# test2_3schematic.net
KiCad netlist of a schematic drawn in EAGLE
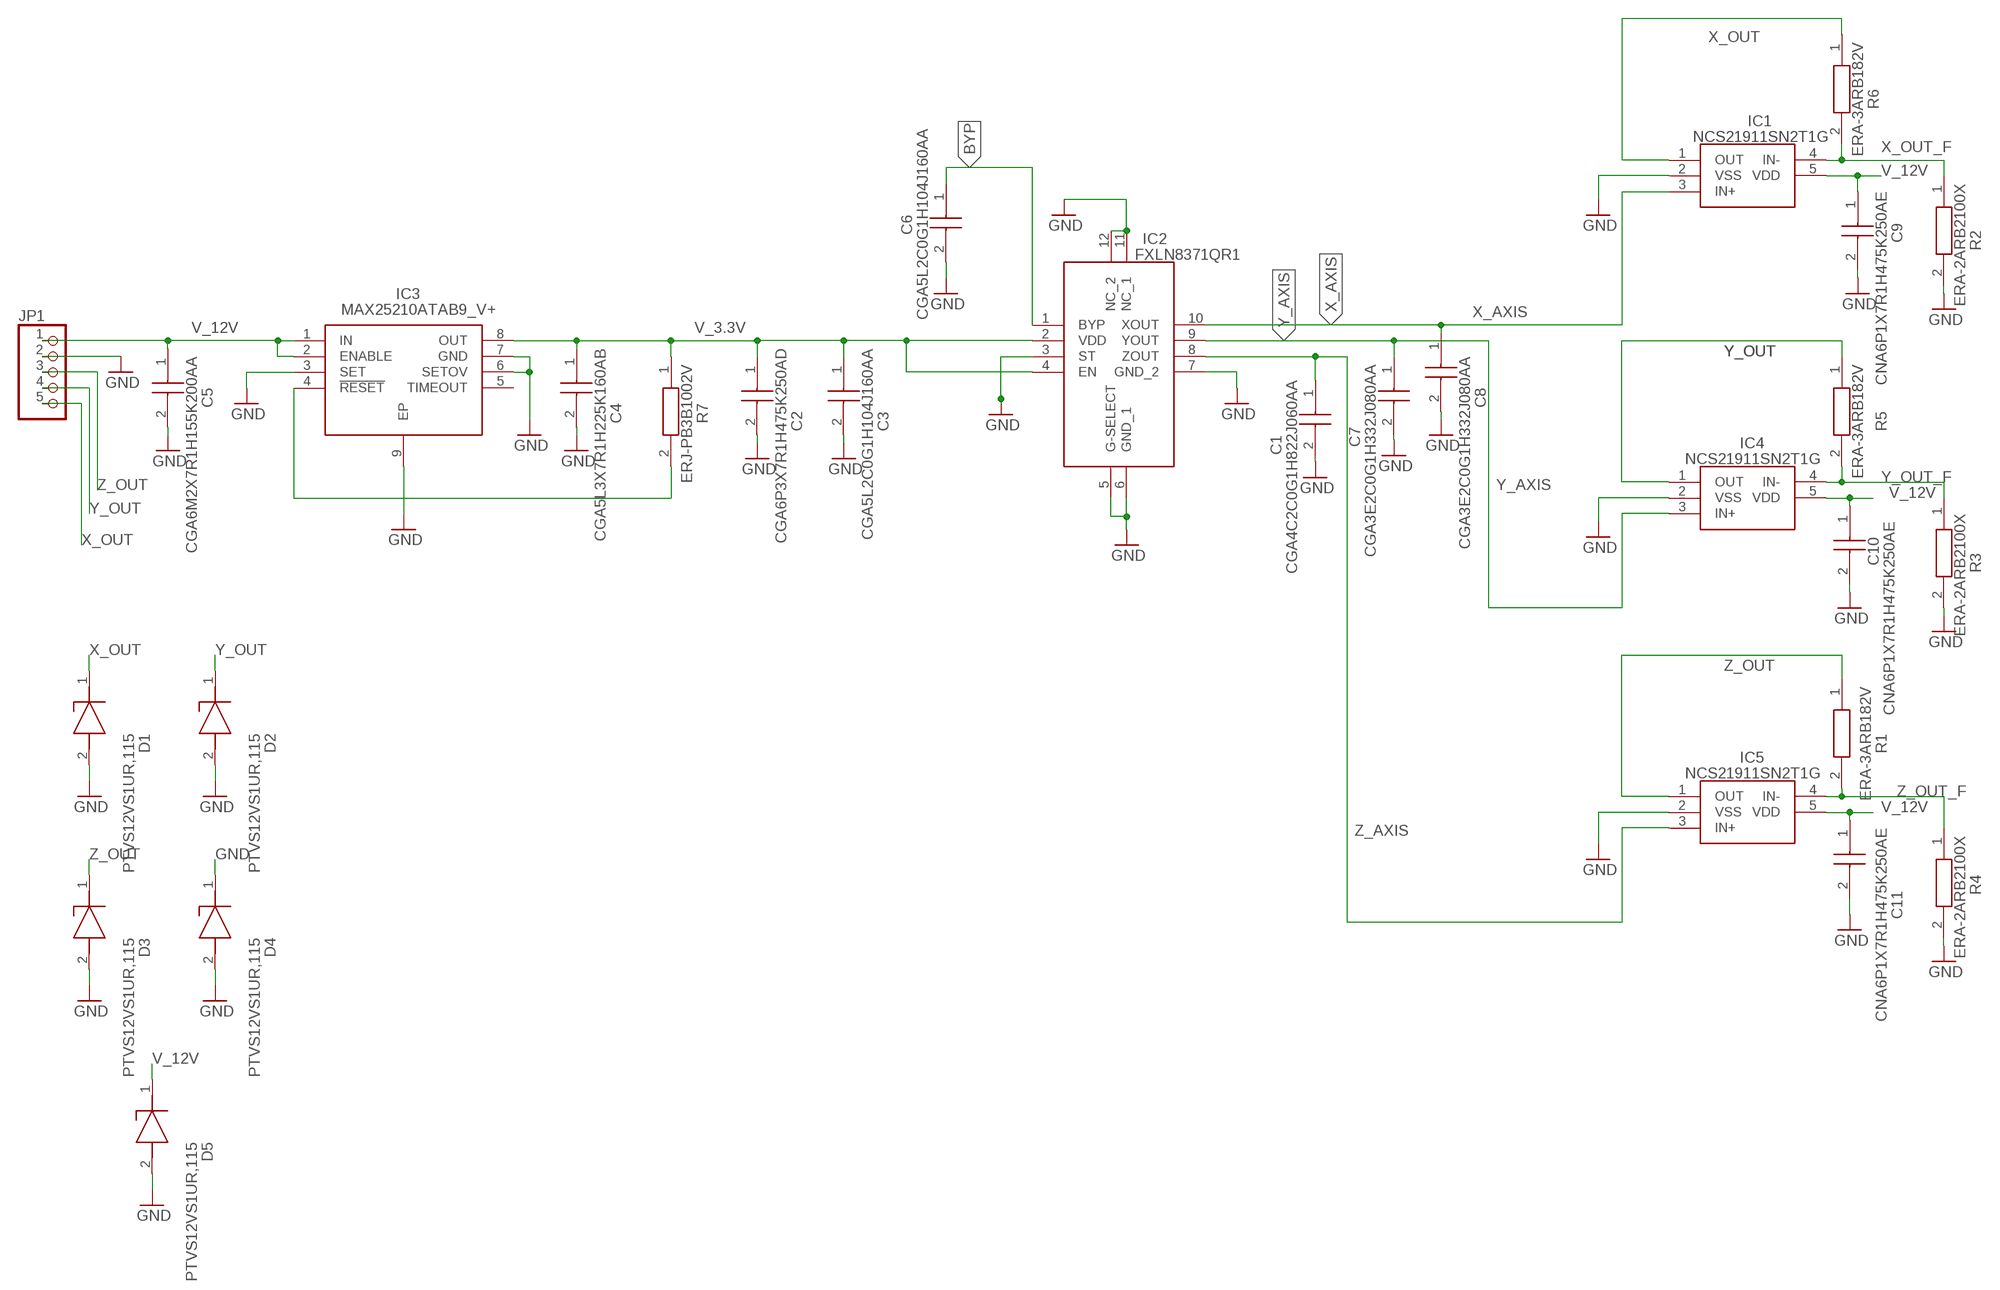
[diagram p0: schematic, sheet 1]

(export (version "E")
  (design (tool "Eeschema 10.0.6"))
  (components
    (comp (ref "C1")
      (value "CGA4C2C0G1H822J060AA")
      (footprint "eagle-import:CAPC2012X145N")
      (libsource (lib "eagle-import") (part "CGA4C2C0G1H822J060AA"))
    )
    (comp (ref "C2")
      (value "CGA6P3X7R1H475K250AD")
      (footprint "eagle-import:CAPC3225X280N")
      (libsource (lib "eagle-import") (part "CGA6P3X7R1H475K250AD"))
    )
    (comp (ref "C3")
      (value "CGA5L2C0G1H104J160AA")
      (footprint "eagle-import:CAPC3216X180N")
      (libsource (lib "eagle-import") (part "CGA5L2C0G1H104J160AA"))
    )
    (comp (ref "C4")
      (value "CGA5L3X7R1H225K160AB")
      (footprint "eagle-import:CAPC3317X190N")
      (libsource (lib "eagle-import") (part "CGA5L3X7R1H225K160AB"))
    )
    (comp (ref "C5")
      (value "CGA6M2X7R1H155K200AA")
      (footprint "eagle-import:CAPC3225X220N")
      (libsource (lib "eagle-import") (part "CGA6M2X7R1H155K200AA"))
    )
    (comp (ref "C6")
      (value "CGA5L2C0G1H104J160AA")
      (footprint "eagle-import:CAPC3216X180N")
      (libsource (lib "eagle-import") (part "CGA5L2C0G1H104J160AA"))
    )
    (comp (ref "C7")
      (value "CGA3E2C0G1H332J080AA")
      (footprint "eagle-import:CAPC1608X90N")
      (libsource (lib "eagle-import") (part "CGA3E2C0G1H332J080AA"))
    )
    (comp (ref "C8")
      (value "CGA3E2C0G1H332J080AA")
      (footprint "eagle-import:CAPC1608X90N")
      (libsource (lib "eagle-import") (part "CGA3E2C0G1H332J080AA"))
    )
    (comp (ref "C9")
      (value "CNA6P1X7R1H475K250AE")
      (footprint "eagle-import:CAPC3225X280N")
      (fields (field (name "MOUSER_PART_NUMBER") "810-CNA6P1X7R1H475K2"))
      (libsource (lib "eagle-import") (part "CNA6P1X7R1H475K250AE"))
    )
    (comp (ref "C10")
      (value "CNA6P1X7R1H475K250AE")
      (footprint "eagle-import:CAPC3225X280N")
      (fields (field (name "MOUSER_PART_NUMBER") "810-CNA6P1X7R1H475K2"))
      (libsource (lib "eagle-import") (part "CNA6P1X7R1H475K250AE"))
    )
    (comp (ref "C11")
      (value "CNA6P1X7R1H475K250AE")
      (footprint "eagle-import:CAPC3225X280N")
      (fields (field (name "MOUSER_PART_NUMBER") "810-CNA6P1X7R1H475K2"))
      (libsource (lib "eagle-import") (part "CNA6P1X7R1H475K250AE"))
    )
    (comp (ref "D1")
      (value "PTVS12VS1UR,115")
      (footprint "eagle-import:SOD123W")
      (fields (field (name "MOUSER_PART_NUMBER") "771-PTVS12VS1UR115"))
      (libsource (lib "eagle-import") (part "PTVS12VS1UR,115"))
    )
    (comp (ref "D2")
      (value "PTVS12VS1UR,115")
      (footprint "eagle-import:SOD123W")
      (fields (field (name "MOUSER_PART_NUMBER") "771-PTVS12VS1UR115"))
      (libsource (lib "eagle-import") (part "PTVS12VS1UR,115"))
    )
    (comp (ref "D3")
      (value "PTVS12VS1UR,115")
      (footprint "eagle-import:SOD123W")
      (fields (field (name "MOUSER_PART_NUMBER") "771-PTVS12VS1UR115"))
      (libsource (lib "eagle-import") (part "PTVS12VS1UR,115"))
    )
    (comp (ref "D4")
      (value "PTVS12VS1UR,115")
      (footprint "eagle-import:SOD123W")
      (fields (field (name "MOUSER_PART_NUMBER") "771-PTVS12VS1UR115"))
      (libsource (lib "eagle-import") (part "PTVS12VS1UR,115"))
    )
    (comp (ref "D5")
      (value "PTVS12VS1UR,115")
      (footprint "eagle-import:SOD123W")
      (fields (field (name "MOUSER_PART_NUMBER") "771-PTVS12VS1UR115"))
      (libsource (lib "eagle-import") (part "PTVS12VS1UR,115"))
    )
    (comp (ref "IC1")
      (value "NCS21911SN2T1G")
      (footprint "eagle-import:SOT95P275X110-5N")
      (fields (field (name "MOUSER_PART_NUMBER") "863-NCS21911SN2T1G"))
      (libsource (lib "eagle-import") (part "NCS21911SN2T1G"))
    )
    (comp (ref "IC2")
      (value "FXLN8371QR1")
      (footprint "eagle-import:QFN65P300X300X100-12N")
      (fields (field (name "MOUSER_PART_NUMBER") "841-FXLN8371QR1"))
      (libsource (lib "eagle-import") (part "FXLN8371QR1"))
    )
    (comp (ref "IC3")
      (value "MAX25210ATAB9_V+")
      (footprint "eagle-import:SON65P300X300X80-9N")
      (fields
        (field (name "MANUFACTURER_PART_NUMBER") "MAX25210ATAB9/V+")
        (field (name "MOUSER_PART_NUMBER") "700-MAX25210ATAB9/V+")
      )
      (libsource (lib "eagle-import") (part "MAX25210ATAB9_V+"))
    )
    (comp (ref "IC4")
      (value "NCS21911SN2T1G")
      (footprint "eagle-import:SOT95P275X110-5N")
      (fields (field (name "MOUSER_PART_NUMBER") "863-NCS21911SN2T1G"))
      (libsource (lib "eagle-import") (part "NCS21911SN2T1G"))
    )
    (comp (ref "IC5")
      (value "NCS21911SN2T1G")
      (footprint "eagle-import:SOT95P275X110-5N")
      (fields (field (name "MOUSER_PART_NUMBER") "863-NCS21911SN2T1G"))
      (libsource (lib "eagle-import") (part "NCS21911SN2T1G"))
    )
    (comp (ref "JP1")
      (value "PINHD-1X5")
      (footprint "eagle-import:1X05")
      (libsource (lib "eagle-import") (part "PINHD-1X5"))
    )
    (comp (ref "R1")
      (value "ERA-3ARB182V")
      (footprint "eagle-import:ERA3A_(0603)")
      (fields (field (name "MOUSER_PART_NUMBER") "667-ERA-3ARB182V"))
      (libsource (lib "eagle-import") (part "ERA-3ARB182V"))
    )
    (comp (ref "R2")
      (value "ERA-2ARB2100X")
      (footprint "eagle-import:RESC1005X40N")
      (libsource (lib "eagle-import") (part "ERA-2ARB2100X"))
    )
    (comp (ref "R3")
      (value "ERA-2ARB2100X")
      (footprint "eagle-import:RESC1005X40N")
      (libsource (lib "eagle-import") (part "ERA-2ARB2100X"))
    )
    (comp (ref "R4")
      (value "ERA-2ARB2100X")
      (footprint "eagle-import:RESC1005X40N")
      (libsource (lib "eagle-import") (part "ERA-2ARB2100X"))
    )
    (comp (ref "R5")
      (value "ERA-3ARB182V")
      (footprint "eagle-import:ERA3A_(0603)")
      (fields (field (name "MOUSER_PART_NUMBER") "667-ERA-3ARB182V"))
      (libsource (lib "eagle-import") (part "ERA-3ARB182V"))
    )
    (comp (ref "R6")
      (value "ERA-3ARB182V")
      (footprint "eagle-import:ERA3A_(0603)")
      (fields (field (name "MOUSER_PART_NUMBER") "667-ERA-3ARB182V"))
      (libsource (lib "eagle-import") (part "ERA-3ARB182V"))
    )
    (comp (ref "R7")
      (value "ERJ-PB3B1002V")
      (footprint "eagle-import:RESC1608X55N")
      (fields (field (name "MOUSER_PART_NUMBER") "667-ERJ-PB3B1002V"))
      (libsource (lib "eagle-import") (part "ERJ-PB3B1002V"))
    )
  )
  (nets
    (net (code "1") (name "/V_3.3V") (class "Default")
      (node (ref "C2") (pin "1") (pinfunction "1_1") (pintype "bidirectional"))
      (node (ref "C3") (pin "1") (pinfunction "1_1") (pintype "bidirectional"))
      (node (ref "C4") (pin "1") (pinfunction "1_1") (pintype "bidirectional"))
      (node (ref "IC2") (pin "2") (pinfunction "VDD_2") (pintype "bidirectional"))
      (node (ref "IC2") (pin "4") (pinfunction "EN_4") (pintype "bidirectional"))
      (node (ref "IC3") (pin "8") (pinfunction "OUT_8") (pintype "bidirectional"))
      (node (ref "R7") (pin "1") (pinfunction "1_1") (pintype "bidirectional"))
    )
    (net (code "2") (name "/V_12V") (class "Default")
      (node (ref "C10") (pin "1") (pinfunction "1_1") (pintype "bidirectional"))
      (node (ref "C11") (pin "1") (pinfunction "1_1") (pintype "bidirectional"))
      (node (ref "C5") (pin "1") (pinfunction "1_1") (pintype "bidirectional"))
      (node (ref "C9") (pin "1") (pinfunction "1_1") (pintype "bidirectional"))
      (node (ref "D5") (pin "1") (pinfunction "K_1") (pintype "bidirectional"))
      (node (ref "IC1") (pin "5") (pinfunction "VDD_5") (pintype "bidirectional"))
      (node (ref "IC3") (pin "1") (pinfunction "IN_1") (pintype "bidirectional"))
      (node (ref "IC3") (pin "2") (pinfunction "ENABLE_2") (pintype "bidirectional"))
      (node (ref "IC4") (pin "5") (pinfunction "VDD_5") (pintype "bidirectional"))
      (node (ref "IC5") (pin "5") (pinfunction "VDD_5") (pintype "bidirectional"))
      (node (ref "JP1") (pin "1") (pinfunction "1_1") (pintype "passive"))
    )
    (net (code "3") (name "/X_OUT") (class "Default")
      (node (ref "D1") (pin "1") (pinfunction "K_1") (pintype "bidirectional"))
      (node (ref "IC1") (pin "1") (pinfunction "OUT_1") (pintype "bidirectional"))
      (node (ref "JP1") (pin "5") (pinfunction "5_5") (pintype "passive"))
      (node (ref "R6") (pin "1") (pinfunction "1_1") (pintype "bidirectional"))
    )
    (net (code "4") (name "/X_OUT_F") (class "Default")
      (node (ref "IC1") (pin "4") (pinfunction "IN-_4") (pintype "bidirectional"))
      (node (ref "R2") (pin "1") (pinfunction "1_1") (pintype "bidirectional"))
      (node (ref "R6") (pin "2") (pinfunction "2_2") (pintype "bidirectional"))
    )
    (net (code "5") (name "/Y_OUT") (class "Default")
      (node (ref "D2") (pin "1") (pinfunction "K_1") (pintype "bidirectional"))
      (node (ref "IC4") (pin "1") (pinfunction "OUT_1") (pintype "bidirectional"))
      (node (ref "JP1") (pin "4") (pinfunction "4_4") (pintype "passive"))
      (node (ref "R5") (pin "1") (pinfunction "1_1") (pintype "bidirectional"))
    )
    (net (code "6") (name "/Y_OUT_F") (class "Default")
      (node (ref "IC4") (pin "4") (pinfunction "IN-_4") (pintype "bidirectional"))
      (node (ref "R3") (pin "1") (pinfunction "1_1") (pintype "bidirectional"))
      (node (ref "R5") (pin "2") (pinfunction "2_2") (pintype "bidirectional"))
    )
    (net (code "7") (name "/Z_AXIS") (class "Default")
      (node (ref "C1") (pin "1") (pinfunction "1_1") (pintype "bidirectional"))
      (node (ref "IC2") (pin "8") (pinfunction "ZOUT_8") (pintype "bidirectional"))
      (node (ref "IC5") (pin "3") (pinfunction "IN+_3") (pintype "bidirectional"))
    )
    (net (code "8") (name "/Z_OUT") (class "Default")
      (node (ref "D3") (pin "1") (pinfunction "K_1") (pintype "bidirectional"))
      (node (ref "IC5") (pin "1") (pinfunction "OUT_1") (pintype "bidirectional"))
      (node (ref "JP1") (pin "3") (pinfunction "3_3") (pintype "passive"))
      (node (ref "R1") (pin "1") (pinfunction "1_1") (pintype "bidirectional"))
    )
    (net (code "9") (name "/Z_OUT_F") (class "Default")
      (node (ref "IC5") (pin "4") (pinfunction "IN-_4") (pintype "bidirectional"))
      (node (ref "R1") (pin "2") (pinfunction "2_2") (pintype "bidirectional"))
      (node (ref "R4") (pin "1") (pinfunction "1_1") (pintype "bidirectional"))
    )
    (net (code "10") (name "BYP") (class "Default")
      (node (ref "C6") (pin "1") (pinfunction "1_1") (pintype "bidirectional"))
      (node (ref "IC2") (pin "1") (pinfunction "BYP_1") (pintype "bidirectional"))
    )
    (net (code "11") (name "GND") (class "Default")
      (node (ref "C1") (pin "2") (pinfunction "2_2") (pintype "bidirectional"))
      (node (ref "C10") (pin "2") (pinfunction "2_2") (pintype "bidirectional"))
      (node (ref "C11") (pin "2") (pinfunction "2_2") (pintype "bidirectional"))
      (node (ref "C2") (pin "2") (pinfunction "2_2") (pintype "bidirectional"))
      (node (ref "C3") (pin "2") (pinfunction "2_2") (pintype "bidirectional"))
      (node (ref "C4") (pin "2") (pinfunction "2_2") (pintype "bidirectional"))
      (node (ref "C5") (pin "2") (pinfunction "2_2") (pintype "bidirectional"))
      (node (ref "C6") (pin "2") (pinfunction "2_2") (pintype "bidirectional"))
      (node (ref "C7") (pin "2") (pinfunction "2_2") (pintype "bidirectional"))
      (node (ref "C8") (pin "2") (pinfunction "2_2") (pintype "bidirectional"))
      (node (ref "C9") (pin "2") (pinfunction "2_2") (pintype "bidirectional"))
      (node (ref "D1") (pin "2") (pinfunction "A_2") (pintype "bidirectional"))
      (node (ref "D2") (pin "2") (pinfunction "A_2") (pintype "bidirectional"))
      (node (ref "D3") (pin "2") (pinfunction "A_2") (pintype "bidirectional"))
      (node (ref "D4") (pin "1") (pinfunction "K_1") (pintype "bidirectional"))
      (node (ref "D4") (pin "2") (pinfunction "A_2") (pintype "bidirectional"))
      (node (ref "D5") (pin "2") (pinfunction "A_2") (pintype "bidirectional"))
      (node (ref "IC1") (pin "2") (pinfunction "VSS_2") (pintype "bidirectional"))
      (node (ref "IC2") (pin "11") (pinfunction "NC_1_11") (pintype "bidirectional"))
      (node (ref "IC2") (pin "12") (pinfunction "NC_2_12") (pintype "bidirectional"))
      (node (ref "IC2") (pin "3") (pinfunction "ST_3") (pintype "bidirectional"))
      (node (ref "IC2") (pin "5") (pinfunction "G-SELECT_5") (pintype "bidirectional"))
      (node (ref "IC2") (pin "6") (pinfunction "GND_1_6") (pintype "bidirectional"))
      (node (ref "IC2") (pin "7") (pinfunction "GND_2_7") (pintype "bidirectional"))
      (node (ref "IC3") (pin "3") (pinfunction "SET_3") (pintype "bidirectional"))
      (node (ref "IC3") (pin "6") (pinfunction "SETOV_6") (pintype "bidirectional"))
      (node (ref "IC3") (pin "7") (pinfunction "GND_7") (pintype "bidirectional"))
      (node (ref "IC3") (pin "9") (pinfunction "EP_9") (pintype "bidirectional"))
      (node (ref "IC4") (pin "2") (pinfunction "VSS_2") (pintype "bidirectional"))
      (node (ref "IC5") (pin "2") (pinfunction "VSS_2") (pintype "bidirectional"))
      (node (ref "JP1") (pin "2") (pinfunction "2_2") (pintype "passive"))
      (node (ref "R2") (pin "2") (pinfunction "2_2") (pintype "bidirectional"))
      (node (ref "R3") (pin "2") (pinfunction "2_2") (pintype "bidirectional"))
      (node (ref "R4") (pin "2") (pinfunction "2_2") (pintype "bidirectional"))
    )
    (net (code "12") (name "Net-(IC3-~{RESET})") (class "Default")
      (node (ref "IC3") (pin "4") (pinfunction "~{RESET}_4") (pintype "bidirectional"))
      (node (ref "R7") (pin "2") (pinfunction "2_2") (pintype "bidirectional"))
    )
    (net (code "13") (name "X_AXIS") (class "Default")
      (node (ref "C8") (pin "1") (pinfunction "1_1") (pintype "bidirectional"))
      (node (ref "IC1") (pin "3") (pinfunction "IN+_3") (pintype "bidirectional"))
      (node (ref "IC2") (pin "10") (pinfunction "XOUT_10") (pintype "bidirectional"))
    )
    (net (code "14") (name "Y_AXIS") (class "Default")
      (node (ref "C7") (pin "1") (pinfunction "1_1") (pintype "bidirectional"))
      (node (ref "IC2") (pin "9") (pinfunction "YOUT_9") (pintype "bidirectional"))
      (node (ref "IC4") (pin "3") (pinfunction "IN+_3") (pintype "bidirectional"))
    )
    (net (code "15") (name "unconnected-(IC3-TIMEOUT-Pad5)") (class "Default")
      (node (ref "IC3") (pin "5") (pinfunction "TIMEOUT_5") (pintype "bidirectional"))
    )
  )
)
